# FPGA2.net
KiCad netlist of a schematic drawn in Altium Designer
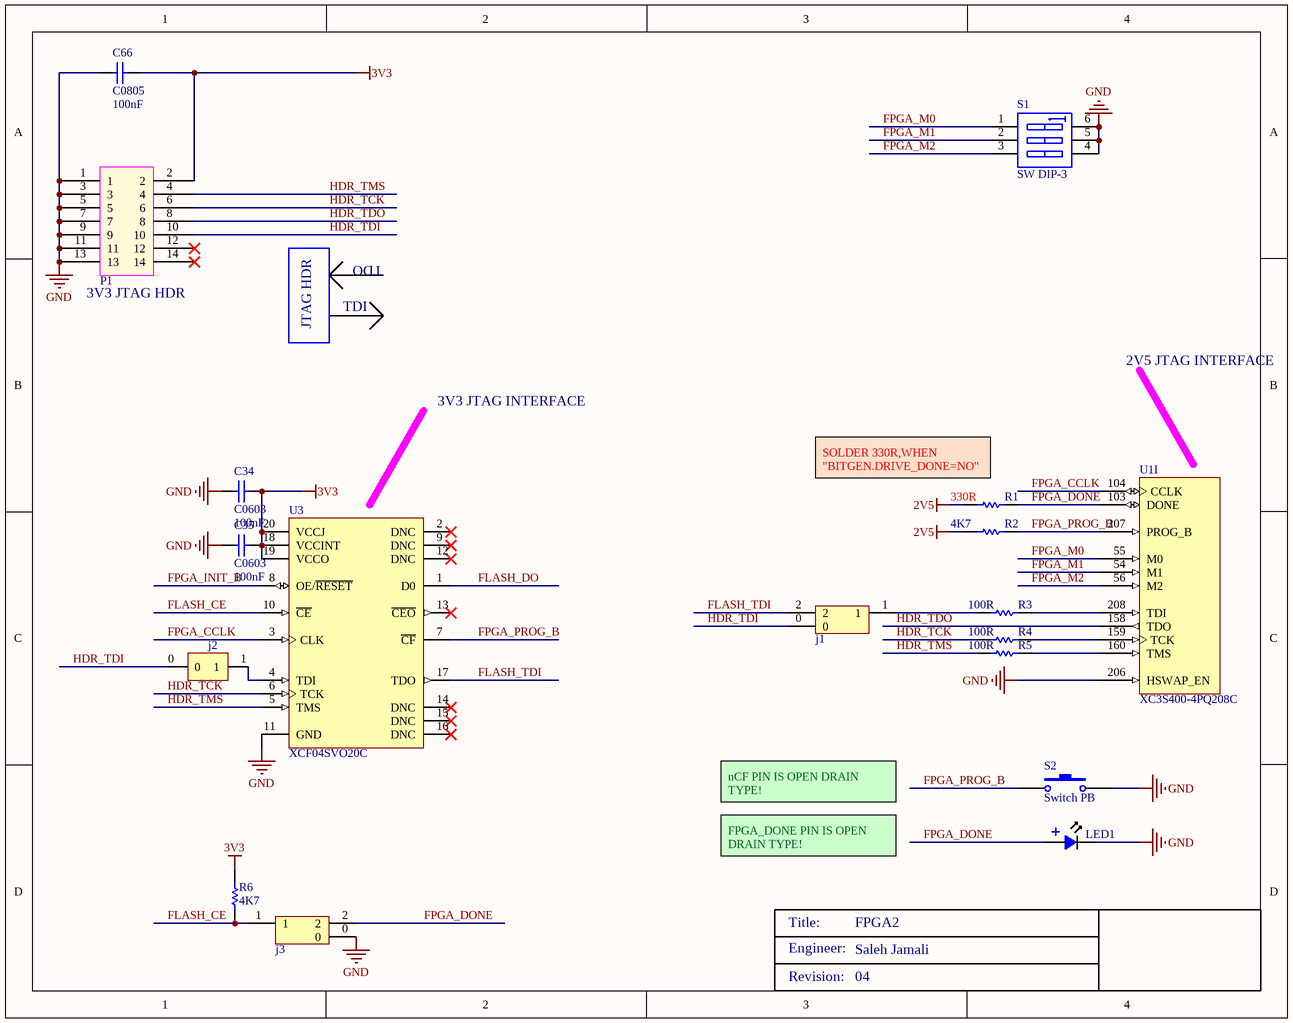
[diagram p0: FPGA2.SchDoc]

(export (version "E")
  (design (tool "Eeschema 10.0.6"))
  (components
    (comp (ref "C34")
      (value "C0603")
      (footprint "0603")
      (description "Ceramic Chip Capacitor - Standard")
      (fields (field (name "ALTIUM_VALUE") "100nF") (field (name "PUBLISHER") "Altium Limited"))
      (libsource (lib "KEMET Chip Capacitor") (part "C0603"))
    )
    (comp (ref "C35")
      (value "C0603")
      (footprint "0603")
      (description "Ceramic Chip Capacitor - Standard")
      (fields (field (name "ALTIUM_VALUE") "100nF") (field (name "PUBLISHER") "Altium Limited"))
      (libsource (lib "KEMET Chip Capacitor") (part "C0603"))
    )
    (comp (ref "C66")
      (value "C0805")
      (footprint "0805")
      (description "Ceramic Chip Capacitor - Standard")
      (fields (field (name "ALTIUM_VALUE") "100nF") (field (name "PUBLISHER") "Altium Limited"))
      (libsource (lib "KEMET Chip Capacitor") (part "C0805"))
    )
    (comp (ref "j1") (value "3pin") (footprint "3PIN") (libsource (lib "") (part "3pin_1")))
    (comp (ref "j2") (value "2pin") (footprint "2PIN") (libsource (lib "jumper2o54mm") (part "2pin")))
    (comp (ref "j3") (value "3pin") (footprint "3PIN") (libsource (lib "jumper2o54mm") (part "3pin")))
    (comp (ref "LED1") (value "LED_SMD") (footprint "LED_805") (libsource (lib "LED_PRJCT") (part "LED_SMD")))
    (comp (ref "P1")
      (value "BoxHeader_14")
      (footprint "14p")
      (libsource (lib "BOX_HEADER") (part "BoxHeader_14"))
    )
    (comp (ref "R1")
      (value "330R")
      (footprint "ERA-0805")
      (fields (field (name "PUBLISHER") "Altium Limited"))
      (libsource (lib "Panasonic Resistor") (part "ERA6Y"))
    )
    (comp (ref "R2")
      (value "4K7")
      (footprint "ERA-0805")
      (fields (field (name "PUBLISHER") "Altium Limited"))
      (libsource (lib "Panasonic Resistor") (part "ERA6Y"))
    )
    (comp (ref "R3")
      (value "100R")
      (footprint "ERA-0805")
      (fields (field (name "PUBLISHER") "Altium Limited"))
      (libsource (lib "Panasonic Resistor") (part "ERA6Y"))
    )
    (comp (ref "R4")
      (value "100R")
      (footprint "ERA-0805")
      (fields (field (name "PUBLISHER") "Altium Limited"))
      (libsource (lib "Panasonic Resistor") (part "ERA6Y"))
    )
    (comp (ref "R5")
      (value "100R")
      (footprint "ERA-0805")
      (fields (field (name "PUBLISHER") "Altium Limited"))
      (libsource (lib "Panasonic Resistor") (part "ERA6Y"))
    )
    (comp (ref "R6")
      (value "4K7")
      (footprint "ERA-0805")
      (fields (field (name "PUBLISHER") "Altium Limited"))
      (libsource (lib "Panasonic Resistor") (part "ERA6Y"))
    )
    (comp (ref "S1")
      (value "SW DIP-3")
      (footprint "DIP-6")
      (description "DIP Switch, 3 Position, SPST")
      (fields (field (name "PUBLISHER") "Altium Limited"))
      (libsource (lib "Miscellaneous Devices") (part "SW DIP-3"))
    )
    (comp (ref "S2")
      (value "Switch PB")
      (footprint "Switch - Push to On")
      (description "Push Button Switch")
      (libsource (lib "MegaLIB") (part "Switch PB"))
    )
    (comp (ref "U1")
      (value "XC3S400-4PQ208C")
      (footprint "PQ208_N")
      (description "Spartan-3 1.2V FPGA, 141 User I/Os, 208-Pin PQFP, Standard Performance, Commercial Grade")
      (libsource (lib "Xilinx Spartan-3") (part "XC3S400-4PQ208C"))
    )
    (comp (ref "U3")
      (value "XCF04SVO20C")
      (footprint "VO20_N")
      (libsource (lib "Xilinx XCF") (part "XCF04SVO20C"))
    )
  )
  (nets
    (net (code "1") (name "/FLASH_CE") (class "Default")
      (node (ref "R6") (pin "1") (pinfunction "1_1") (pintype "passive"))
      (node (ref "U3") (pin "10") (pinfunction "~{CE}_10") (pintype "input"))
      (node (ref "j3") (pin "1") (pinfunction "1_1") (pintype "passive"))
    )
    (net (code "2") (name "/FLASH_DO") (class "Default")
      (node (ref "U3") (pin "1") (pinfunction "D0_1") (pintype "tri_state"))
    )
    (net (code "3") (name "/FLASH_TDI") (class "Default")
      (node (ref "U3") (pin "17") (pinfunction "TDO_17") (pintype "output"))
      (node (ref "j1") (pin "2") (pinfunction "2_2") (pintype "passive"))
    )
    (net (code "4") (name "/FPGA_CCLK") (class "Default")
      (node (ref "U1") (pin "104") (pinfunction "CCLK_104") (pintype "bidirectional"))
      (node (ref "U3") (pin "3") (pinfunction "CLK_3") (pintype "input"))
    )
    (net (code "5") (name "/FPGA_DONE") (class "Default")
      (node (ref "LED1") (pin "1") (pinfunction "1_1") (pintype "passive"))
      (node (ref "R1") (pin "2") (pinfunction "2_2") (pintype "passive"))
      (node (ref "U1") (pin "103") (pinfunction "DONE_103") (pintype "bidirectional"))
      (node (ref "j3") (pin "2") (pinfunction "2_2") (pintype "passive"))
    )
    (net (code "6") (name "/FPGA_INIT_B") (class "Default")
      (node (ref "U3") (pin "8") (pinfunction "OE/~{RESET}_8") (pintype "bidirectional"))
    )
    (net (code "7") (name "/FPGA_M0") (class "Default")
      (node (ref "S1") (pin "1") (pinfunction "A1_1") (pintype "passive"))
      (node (ref "U1") (pin "55") (pinfunction "M0_55") (pintype "input"))
    )
    (net (code "8") (name "/FPGA_M1") (class "Default")
      (node (ref "S1") (pin "2") (pinfunction "A2_2") (pintype "passive"))
      (node (ref "U1") (pin "54") (pinfunction "M1_54") (pintype "input"))
    )
    (net (code "9") (name "/FPGA_M2") (class "Default")
      (node (ref "S1") (pin "3") (pinfunction "A3_3") (pintype "passive"))
      (node (ref "U1") (pin "56") (pinfunction "M2_56") (pintype "input"))
    )
    (net (code "10") (name "/FPGA_PROG_B") (class "Default")
      (node (ref "R2") (pin "2") (pinfunction "2_2") (pintype "passive"))
      (node (ref "S2") (pin "1") (pinfunction "1_1") (pintype "passive"))
      (node (ref "U1") (pin "207") (pinfunction "PROG_B_207") (pintype "input"))
      (node (ref "U3") (pin "7") (pinfunction "~{CF}_7") (pintype "open_collector"))
    )
    (net (code "11") (name "/HDR_TCK") (class "Default")
      (node (ref "P1") (pin "6") (pinfunction "6_6") (pintype "passive"))
      (node (ref "R4") (pin "1") (pinfunction "1_1") (pintype "passive"))
      (node (ref "U3") (pin "6") (pinfunction "TCK_6") (pintype "input"))
    )
    (net (code "12") (name "/HDR_TDI") (class "Default")
      (node (ref "P1") (pin "10") (pinfunction "10_10") (pintype "passive"))
      (node (ref "j1") (pin "0") (pinfunction "0_0") (pintype "passive"))
      (node (ref "j2") (pin "0") (pinfunction "0_0") (pintype "passive"))
    )
    (net (code "13") (name "/HDR_TDO") (class "Default")
      (node (ref "P1") (pin "8") (pinfunction "8_8") (pintype "passive"))
      (node (ref "U1") (pin "158") (pinfunction "TDO_158") (pintype "output"))
    )
    (net (code "14") (name "/HDR_TMS") (class "Default")
      (node (ref "P1") (pin "4") (pinfunction "4_4") (pintype "passive"))
      (node (ref "R5") (pin "1") (pinfunction "1_1") (pintype "passive"))
      (node (ref "U3") (pin "5") (pinfunction "TMS_5") (pintype "input"))
    )
    (net (code "15") (name "2V5") (class "Default")
      (node (ref "R1") (pin "1") (pinfunction "1_1") (pintype "passive"))
      (node (ref "R2") (pin "1") (pinfunction "1_1") (pintype "passive"))
    )
    (net (code "16") (name "3V3") (class "Default")
      (node (ref "C34") (pin "1") (pinfunction "1_1") (pintype "passive"))
      (node (ref "C35") (pin "1") (pinfunction "1_1") (pintype "passive"))
      (node (ref "C66") (pin "2") (pinfunction "2_2") (pintype "passive"))
      (node (ref "P1") (pin "2") (pinfunction "2_2") (pintype "passive"))
      (node (ref "R6") (pin "2") (pinfunction "2_2") (pintype "passive"))
      (node (ref "U3") (pin "18") (pinfunction "VCCINT_18") (pintype "power_in"))
      (node (ref "U3") (pin "19") (pinfunction "VCCO_19") (pintype "power_in"))
      (node (ref "U3") (pin "20") (pinfunction "VCCJ_20") (pintype "power_in"))
    )
    (net (code "17") (name "GND") (class "Default")
      (node (ref "C34") (pin "2") (pinfunction "2_2") (pintype "passive"))
      (node (ref "C35") (pin "2") (pinfunction "2_2") (pintype "passive"))
      (node (ref "C66") (pin "1") (pinfunction "1_1") (pintype "passive"))
      (node (ref "LED1") (pin "2") (pinfunction "2_2") (pintype "passive"))
      (node (ref "P1") (pin "1") (pinfunction "1_1") (pintype "passive"))
      (node (ref "P1") (pin "11") (pinfunction "11_11") (pintype "passive"))
      (node (ref "P1") (pin "13") (pinfunction "13_13") (pintype "passive"))
      (node (ref "P1") (pin "3") (pinfunction "3_3") (pintype "passive"))
      (node (ref "P1") (pin "5") (pinfunction "5_5") (pintype "passive"))
      (node (ref "P1") (pin "7") (pinfunction "7_7") (pintype "passive"))
      (node (ref "P1") (pin "9") (pinfunction "9_9") (pintype "passive"))
      (node (ref "S1") (pin "4") (pinfunction "B3_4") (pintype "passive"))
      (node (ref "S1") (pin "5") (pinfunction "B2_5") (pintype "passive"))
      (node (ref "S1") (pin "6") (pinfunction "B1_6") (pintype "passive"))
      (node (ref "S2") (pin "2") (pinfunction "2_2") (pintype "passive"))
      (node (ref "U1") (pin "206") (pinfunction "HSWAP_EN_206") (pintype "input"))
      (node (ref "U3") (pin "11") (pinfunction "GND_11") (pintype "power_in"))
      (node (ref "j3") (pin "0") (pinfunction "0_0") (pintype "passive"))
    )
    (net (code "18") (name "Net-(R3-Pad1)") (class "Default")
      (node (ref "R3") (pin "1") (pinfunction "1_1") (pintype "passive"))
      (node (ref "j1") (pin "1") (pinfunction "1_1") (pintype "passive"))
    )
    (net (code "19") (name "Net-(U1I-TCK)") (class "Default")
      (node (ref "R4") (pin "2") (pinfunction "2_2") (pintype "passive"))
      (node (ref "U1") (pin "159") (pinfunction "TCK_159") (pintype "input"))
    )
    (net (code "20") (name "Net-(U1I-TDI)") (class "Default")
      (node (ref "R3") (pin "2") (pinfunction "2_2") (pintype "passive"))
      (node (ref "U1") (pin "208") (pinfunction "TDI_208") (pintype "input"))
    )
    (net (code "21") (name "Net-(U1I-TMS)") (class "Default")
      (node (ref "R5") (pin "2") (pinfunction "2_2") (pintype "passive"))
      (node (ref "U1") (pin "160") (pinfunction "TMS_160") (pintype "input"))
    )
    (net (code "22") (name "Net-(U3-TDI)") (class "Default")
      (node (ref "U3") (pin "4") (pinfunction "TDI_4") (pintype "input"))
      (node (ref "j2") (pin "1") (pinfunction "1_1") (pintype "passive"))
    )
    (net (code "23") (name "unconnected-(P1-Pad12)") (class "Default")
      (node (ref "P1") (pin "12") (pinfunction "12_12") (pintype "passive+no_connect"))
    )
    (net (code "24") (name "unconnected-(P1-Pad14)") (class "Default")
      (node (ref "P1") (pin "14") (pinfunction "14_14") (pintype "passive+no_connect"))
    )
    (net (code "25") (name "unconnected-(U3-DNC-Pad2)") (class "Default")
      (node (ref "U3") (pin "2") (pinfunction "DNC_2") (pintype "passive+no_connect"))
    )
    (net (code "26") (name "unconnected-(U3-DNC-Pad9)") (class "Default")
      (node (ref "U3") (pin "9") (pinfunction "DNC_9") (pintype "passive+no_connect"))
    )
    (net (code "27") (name "unconnected-(U3-DNC-Pad12)") (class "Default")
      (node (ref "U3") (pin "12") (pinfunction "DNC_12") (pintype "passive+no_connect"))
    )
    (net (code "28") (name "unconnected-(U3-DNC-Pad14)") (class "Default")
      (node (ref "U3") (pin "14") (pinfunction "DNC_14") (pintype "passive+no_connect"))
    )
    (net (code "29") (name "unconnected-(U3-DNC-Pad15)") (class "Default")
      (node (ref "U3") (pin "15") (pinfunction "DNC_15") (pintype "passive+no_connect"))
    )
    (net (code "30") (name "unconnected-(U3-DNC-Pad16)") (class "Default")
      (node (ref "U3") (pin "16") (pinfunction "DNC_16") (pintype "passive+no_connect"))
    )
    (net (code "31") (name "unconnected-(U3-~{CEO}-Pad13)") (class "Default")
      (node (ref "U3") (pin "13") (pinfunction "~{CEO}_13") (pintype "output+no_connect"))
    )
  )
)
